# a26-flashcart.net
KiCad netlist of a schematic drawn in EAGLE
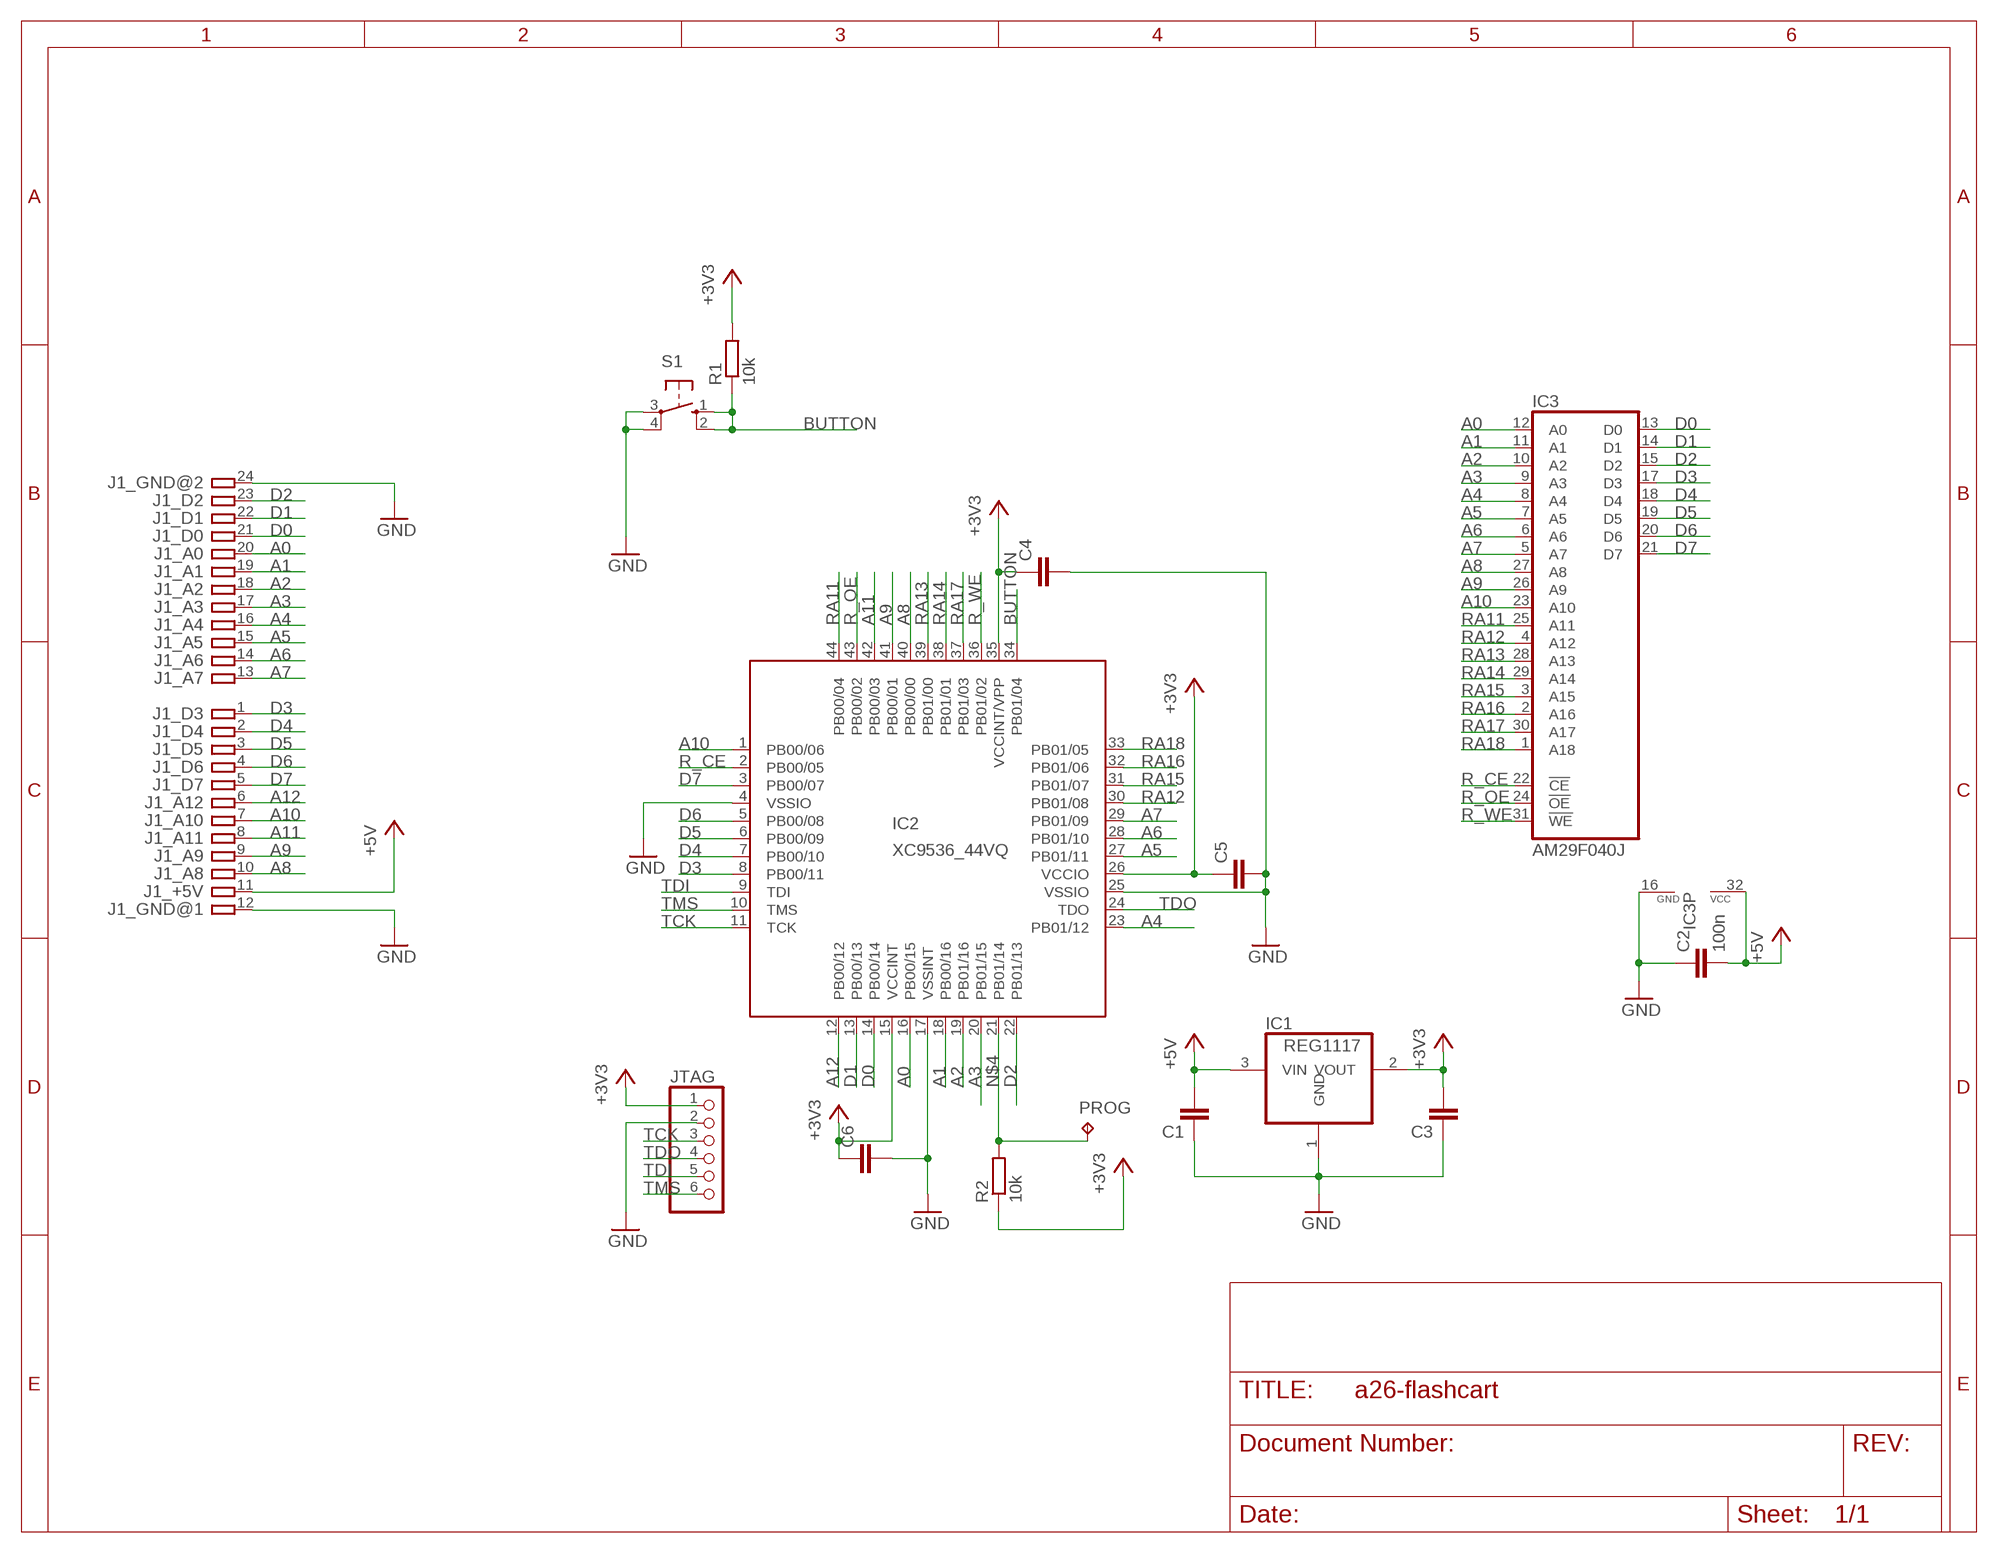
[diagram p0: schematic, sheet 1]

(export (version "E")
  (design (tool "Eeschema 10.0.6"))
  (components
    (comp (ref "C1")
      (value "C-EUC0603")
      (footprint "eagle-import:C0603")
      (libsource (lib "eagle-import") (part "C-EUC0603"))
    )
    (comp (ref "C2")
      (value "100n")
      (footprint "eagle-import:C0603")
      (libsource (lib "eagle-import") (part "C-EUC0603"))
    )
    (comp (ref "C3")
      (value "C-EUC0603")
      (footprint "eagle-import:C0603")
      (libsource (lib "eagle-import") (part "C-EUC0603"))
    )
    (comp (ref "C4")
      (value "C-EUC0603")
      (footprint "eagle-import:C0603")
      (libsource (lib "eagle-import") (part "C-EUC0603"))
    )
    (comp (ref "C5")
      (value "C-EUC0603")
      (footprint "eagle-import:C0603")
      (libsource (lib "eagle-import") (part "C-EUC0603"))
    )
    (comp (ref "C6")
      (value "C-EUC0603")
      (footprint "eagle-import:C0603")
      (libsource (lib "eagle-import") (part "C-EUC0603"))
    )
    (comp (ref "IC1")
      (value "REG1117")
      (footprint "eagle-import:SOT223")
      (libsource (lib "eagle-import") (part "REG1117"))
    )
    (comp (ref "IC2")
      (value "XC9536_44VQ")
      (footprint "eagle-import:SQFP-S-10X10-44")
      (fields (field (name "MPN") "XC9536-15VQG44C"))
      (libsource (lib "eagle-import") (part "XC9536_44VQ"))
    )
    (comp (ref "IC3")
      (value "AM29F040J")
      (footprint "eagle-import:PLCC32R")
      (libsource (lib "eagle-import") (part "AM29F040J"))
    )
    (comp (ref "J1")
      (value "ATARI-2600-SMALL")
      (footprint "eagle-import:ATARI-2600-SMALL")
      (libsource (lib "eagle-import") (part "ATARI-2600-SMALL"))
    )
    (comp (ref "JTAG")
      (value "PINHD-1X6")
      (footprint "eagle-import:1X06")
      (libsource (lib "eagle-import") (part "PINHD-1X6"))
    )
    (comp (ref "PROG")
      (value "TPTP15R")
      (footprint "eagle-import:TP15R")
      (libsource (lib "eagle-import") (part "TPTP15R"))
    )
    (comp (ref "R1")
      (value "10k")
      (footprint "eagle-import:R0603")
      (libsource (lib "eagle-import") (part "R-EU_R0603"))
    )
    (comp (ref "R2")
      (value "10k")
      (footprint "eagle-import:R0603")
      (libsource (lib "eagle-import") (part "R-EU_R0603"))
    )
    (comp (ref "S1")
      (value "10-XX")
      (footprint "eagle-import:B3F-10XX")
      (fields (field (name "MPN") "B3F-1000"))
      (libsource (lib "eagle-import") (part "10-XX"))
    )
  )
  (nets
    (net (code "1") (name "+3V3") (class "Default")
      (node (ref "C3") (pin "2") (pinfunction "2_2") (pintype "passive"))
      (node (ref "C4") (pin "1") (pinfunction "1_1") (pintype "passive"))
      (node (ref "C5") (pin "1") (pinfunction "1_1") (pintype "passive"))
      (node (ref "C6") (pin "1") (pinfunction "1_1") (pintype "passive"))
      (node (ref "IC1") (pin "2") (pinfunction "VOUT_2") (pintype "output"))
      (node (ref "IC2") (pin "15") (pinfunction "VCCINT_15") (pintype "power_in"))
      (node (ref "IC2") (pin "26") (pinfunction "VCCIO_26") (pintype "power_in"))
      (node (ref "IC2") (pin "35") (pinfunction "VCCINT/VPP_35") (pintype "input"))
      (node (ref "JTAG") (pin "1") (pinfunction "1_1") (pintype "passive"))
      (node (ref "R1") (pin "2") (pinfunction "2_2") (pintype "passive"))
      (node (ref "R2") (pin "1") (pinfunction "1_1") (pintype "passive"))
    )
    (net (code "2") (name "+5V") (class "Default")
      (node (ref "C1") (pin "2") (pinfunction "2_2") (pintype "passive"))
      (node (ref "C2") (pin "2") (pinfunction "2_2") (pintype "passive"))
      (node (ref "IC1") (pin "3") (pinfunction "VIN_3") (pintype "input"))
      (node (ref "IC3") (pin "32") (pinfunction "VCC_32") (pintype "power_in"))
      (node (ref "J1") (pin "11") (pinfunction "P_11") (pintype "bidirectional"))
    )
    (net (code "3") (name "/A0") (class "Default")
      (node (ref "IC2") (pin "16") (pinfunction "PB00/15_16") (pintype "bidirectional"))
      (node (ref "IC3") (pin "12") (pinfunction "A0_12") (pintype "input"))
      (node (ref "J1") (pin "20") (pinfunction "P_20") (pintype "bidirectional"))
    )
    (net (code "4") (name "/A1") (class "Default")
      (node (ref "IC2") (pin "18") (pinfunction "PB00/16_18") (pintype "bidirectional"))
      (node (ref "IC3") (pin "11") (pinfunction "A1_11") (pintype "input"))
      (node (ref "J1") (pin "19") (pinfunction "P_19") (pintype "bidirectional"))
    )
    (net (code "5") (name "/A2") (class "Default")
      (node (ref "IC2") (pin "19") (pinfunction "PB01/16_19") (pintype "bidirectional"))
      (node (ref "IC3") (pin "10") (pinfunction "A2_10") (pintype "input"))
      (node (ref "J1") (pin "18") (pinfunction "P_18") (pintype "bidirectional"))
    )
    (net (code "6") (name "/A3") (class "Default")
      (node (ref "IC2") (pin "20") (pinfunction "PB01/15_20") (pintype "bidirectional"))
      (node (ref "IC3") (pin "9") (pinfunction "A3_9") (pintype "input"))
      (node (ref "J1") (pin "17") (pinfunction "P_17") (pintype "bidirectional"))
    )
    (net (code "7") (name "/A4") (class "Default")
      (node (ref "IC2") (pin "23") (pinfunction "PB01/12_23") (pintype "bidirectional"))
      (node (ref "IC3") (pin "8") (pinfunction "A4_8") (pintype "input"))
      (node (ref "J1") (pin "16") (pinfunction "P_16") (pintype "bidirectional"))
    )
    (net (code "8") (name "/A5") (class "Default")
      (node (ref "IC2") (pin "27") (pinfunction "PB01/11_27") (pintype "bidirectional"))
      (node (ref "IC3") (pin "7") (pinfunction "A5_7") (pintype "input"))
      (node (ref "J1") (pin "15") (pinfunction "P_15") (pintype "bidirectional"))
    )
    (net (code "9") (name "/A6") (class "Default")
      (node (ref "IC2") (pin "28") (pinfunction "PB01/10_28") (pintype "bidirectional"))
      (node (ref "IC3") (pin "6") (pinfunction "A6_6") (pintype "input"))
      (node (ref "J1") (pin "14") (pinfunction "P_14") (pintype "bidirectional"))
    )
    (net (code "10") (name "/A7") (class "Default")
      (node (ref "IC2") (pin "29") (pinfunction "PB01/09_29") (pintype "bidirectional"))
      (node (ref "IC3") (pin "5") (pinfunction "A7_5") (pintype "input"))
      (node (ref "J1") (pin "13") (pinfunction "P_13") (pintype "bidirectional"))
    )
    (net (code "11") (name "/A8") (class "Default")
      (node (ref "IC2") (pin "40") (pinfunction "PB00/00_40") (pintype "bidirectional"))
      (node (ref "IC3") (pin "27") (pinfunction "A8_27") (pintype "input"))
      (node (ref "J1") (pin "10") (pinfunction "P_10") (pintype "bidirectional"))
    )
    (net (code "12") (name "/A9") (class "Default")
      (node (ref "IC2") (pin "41") (pinfunction "PB00/01_41") (pintype "bidirectional"))
      (node (ref "IC3") (pin "26") (pinfunction "A9_26") (pintype "input"))
      (node (ref "J1") (pin "9") (pinfunction "P_9") (pintype "bidirectional"))
    )
    (net (code "13") (name "/A10") (class "Default")
      (node (ref "IC2") (pin "1") (pinfunction "PB00/06_1") (pintype "bidirectional"))
      (node (ref "IC3") (pin "23") (pinfunction "A10_23") (pintype "input"))
      (node (ref "J1") (pin "7") (pinfunction "P_7") (pintype "bidirectional"))
    )
    (net (code "14") (name "/A11") (class "Default")
      (node (ref "IC2") (pin "42") (pinfunction "PB00/03_42") (pintype "bidirectional"))
      (node (ref "J1") (pin "8") (pinfunction "P_8") (pintype "bidirectional"))
    )
    (net (code "15") (name "/A12") (class "Default")
      (node (ref "IC2") (pin "12") (pinfunction "PB00/12_12") (pintype "bidirectional"))
      (node (ref "J1") (pin "6") (pinfunction "P_6") (pintype "bidirectional"))
    )
    (net (code "16") (name "/BUTTON") (class "Default")
      (node (ref "IC2") (pin "34") (pinfunction "PB01/04_34") (pintype "bidirectional"))
      (node (ref "R1") (pin "1") (pinfunction "1_1") (pintype "passive"))
      (node (ref "S1") (pin "1") (pinfunction "S_1") (pintype "passive"))
      (node (ref "S1") (pin "2") (pinfunction "S1_2") (pintype "passive"))
    )
    (net (code "17") (name "/D0") (class "Default")
      (node (ref "IC2") (pin "14") (pinfunction "PB00/14_14") (pintype "bidirectional"))
      (node (ref "IC3") (pin "13") (pinfunction "D0_13") (pintype "tri_state"))
      (node (ref "J1") (pin "21") (pinfunction "P_21") (pintype "bidirectional"))
    )
    (net (code "18") (name "/D1") (class "Default")
      (node (ref "IC2") (pin "13") (pinfunction "PB00/13_13") (pintype "bidirectional"))
      (node (ref "IC3") (pin "14") (pinfunction "D1_14") (pintype "tri_state"))
      (node (ref "J1") (pin "22") (pinfunction "P_22") (pintype "bidirectional"))
    )
    (net (code "19") (name "/D2") (class "Default")
      (node (ref "IC2") (pin "22") (pinfunction "PB01/13_22") (pintype "bidirectional"))
      (node (ref "IC3") (pin "15") (pinfunction "D2_15") (pintype "tri_state"))
      (node (ref "J1") (pin "23") (pinfunction "P_23") (pintype "bidirectional"))
    )
    (net (code "20") (name "/D3") (class "Default")
      (node (ref "IC2") (pin "8") (pinfunction "PB00/11_8") (pintype "bidirectional"))
      (node (ref "IC3") (pin "17") (pinfunction "D3_17") (pintype "tri_state"))
      (node (ref "J1") (pin "1") (pinfunction "P_1") (pintype "bidirectional"))
    )
    (net (code "21") (name "/D4") (class "Default")
      (node (ref "IC2") (pin "7") (pinfunction "PB00/10_7") (pintype "bidirectional"))
      (node (ref "IC3") (pin "18") (pinfunction "D4_18") (pintype "tri_state"))
      (node (ref "J1") (pin "2") (pinfunction "P_2") (pintype "bidirectional"))
    )
    (net (code "22") (name "/D5") (class "Default")
      (node (ref "IC2") (pin "6") (pinfunction "PB00/09_6") (pintype "bidirectional"))
      (node (ref "IC3") (pin "19") (pinfunction "D5_19") (pintype "tri_state"))
      (node (ref "J1") (pin "3") (pinfunction "P_3") (pintype "bidirectional"))
    )
    (net (code "23") (name "/D6") (class "Default")
      (node (ref "IC2") (pin "5") (pinfunction "PB00/08_5") (pintype "bidirectional"))
      (node (ref "IC3") (pin "20") (pinfunction "D6_20") (pintype "tri_state"))
      (node (ref "J1") (pin "4") (pinfunction "P_4") (pintype "bidirectional"))
    )
    (net (code "24") (name "/D7") (class "Default")
      (node (ref "IC2") (pin "3") (pinfunction "PB00/07_3") (pintype "bidirectional"))
      (node (ref "IC3") (pin "21") (pinfunction "D7_21") (pintype "tri_state"))
      (node (ref "J1") (pin "5") (pinfunction "P_5") (pintype "bidirectional"))
    )
    (net (code "25") (name "/N$4") (class "Default")
      (node (ref "IC2") (pin "21") (pinfunction "PB01/14_21") (pintype "bidirectional"))
      (node (ref "PROG") (pin "TP") (pinfunction "TP_TP") (pintype "input"))
      (node (ref "R2") (pin "2") (pinfunction "2_2") (pintype "passive"))
    )
    (net (code "26") (name "/RA11") (class "Default")
      (node (ref "IC2") (pin "44") (pinfunction "PB00/04_44") (pintype "bidirectional"))
      (node (ref "IC3") (pin "25") (pinfunction "A11_25") (pintype "input"))
    )
    (net (code "27") (name "/RA12") (class "Default")
      (node (ref "IC2") (pin "30") (pinfunction "PB01/08_30") (pintype "bidirectional"))
      (node (ref "IC3") (pin "4") (pinfunction "A12_4") (pintype "input"))
    )
    (net (code "28") (name "/RA13") (class "Default")
      (node (ref "IC2") (pin "39") (pinfunction "PB01/00_39") (pintype "bidirectional"))
      (node (ref "IC3") (pin "28") (pinfunction "A13_28") (pintype "input"))
    )
    (net (code "29") (name "/RA14") (class "Default")
      (node (ref "IC2") (pin "38") (pinfunction "PB01/01_38") (pintype "bidirectional"))
      (node (ref "IC3") (pin "29") (pinfunction "A14_29") (pintype "input"))
    )
    (net (code "30") (name "/RA15") (class "Default")
      (node (ref "IC2") (pin "31") (pinfunction "PB01/07_31") (pintype "bidirectional"))
      (node (ref "IC3") (pin "3") (pinfunction "A15_3") (pintype "input"))
    )
    (net (code "31") (name "/RA16") (class "Default")
      (node (ref "IC2") (pin "32") (pinfunction "PB01/06_32") (pintype "bidirectional"))
      (node (ref "IC3") (pin "2") (pinfunction "A16_2") (pintype "input"))
    )
    (net (code "32") (name "/RA17") (class "Default")
      (node (ref "IC2") (pin "37") (pinfunction "PB01/03_37") (pintype "bidirectional"))
      (node (ref "IC3") (pin "30") (pinfunction "A17_30") (pintype "input"))
    )
    (net (code "33") (name "/RA18") (class "Default")
      (node (ref "IC2") (pin "33") (pinfunction "PB01/05_33") (pintype "bidirectional"))
      (node (ref "IC3") (pin "1") (pinfunction "A18_1") (pintype "input"))
    )
    (net (code "34") (name "/R_CE") (class "Default")
      (node (ref "IC2") (pin "2") (pinfunction "PB00/05_2") (pintype "bidirectional"))
      (node (ref "IC3") (pin "22") (pinfunction "~{CE}_22") (pintype "input"))
    )
    (net (code "35") (name "/R_OE") (class "Default")
      (node (ref "IC2") (pin "43") (pinfunction "PB00/02_43") (pintype "bidirectional"))
      (node (ref "IC3") (pin "24") (pinfunction "~{OE}_24") (pintype "input"))
    )
    (net (code "36") (name "/R_WE") (class "Default")
      (node (ref "IC2") (pin "36") (pinfunction "PB01/02_36") (pintype "bidirectional"))
      (node (ref "IC3") (pin "31") (pinfunction "~{WE}_31") (pintype "input"))
    )
    (net (code "37") (name "/TCK") (class "Default")
      (node (ref "IC2") (pin "11") (pinfunction "TCK_11") (pintype "input"))
      (node (ref "JTAG") (pin "3") (pinfunction "3_3") (pintype "passive"))
    )
    (net (code "38") (name "/TDI") (class "Default")
      (node (ref "IC2") (pin "9") (pinfunction "TDI_9") (pintype "input"))
      (node (ref "JTAG") (pin "5") (pinfunction "5_5") (pintype "passive"))
    )
    (net (code "39") (name "/TDO") (class "Default")
      (node (ref "IC2") (pin "24") (pinfunction "TDO_24") (pintype "output"))
      (node (ref "JTAG") (pin "4") (pinfunction "4_4") (pintype "passive"))
    )
    (net (code "40") (name "/TMS") (class "Default")
      (node (ref "IC2") (pin "10") (pinfunction "TMS_10") (pintype "input"))
      (node (ref "JTAG") (pin "6") (pinfunction "6_6") (pintype "passive"))
    )
    (net (code "41") (name "GND") (class "Default")
      (node (ref "C1") (pin "1") (pinfunction "1_1") (pintype "passive"))
      (node (ref "C2") (pin "1") (pinfunction "1_1") (pintype "passive"))
      (node (ref "C3") (pin "1") (pinfunction "1_1") (pintype "passive"))
      (node (ref "C4") (pin "2") (pinfunction "2_2") (pintype "passive"))
      (node (ref "C5") (pin "2") (pinfunction "2_2") (pintype "passive"))
      (node (ref "C6") (pin "2") (pinfunction "2_2") (pintype "passive"))
      (node (ref "IC1") (pin "1") (pinfunction "GND_1") (pintype "power_in"))
      (node (ref "IC2") (pin "17") (pinfunction "VSSINT_17") (pintype "power_in"))
      (node (ref "IC2") (pin "25") (pinfunction "VSSIO_25") (pintype "power_in"))
      (node (ref "IC2") (pin "4") (pinfunction "VSSIO_4") (pintype "power_in"))
      (node (ref "IC3") (pin "16") (pinfunction "GND_16") (pintype "power_in"))
      (node (ref "J1") (pin "12") (pinfunction "P_12") (pintype "bidirectional"))
      (node (ref "J1") (pin "24") (pinfunction "P_24") (pintype "bidirectional"))
      (node (ref "JTAG") (pin "2") (pinfunction "2_2") (pintype "passive"))
      (node (ref "S1") (pin "3") (pinfunction "P_3") (pintype "passive"))
      (node (ref "S1") (pin "4") (pinfunction "P1_4") (pintype "passive"))
    )
  )
)
